# equalizer.net
KiCad netlist of a schematic drawn in EAGLE
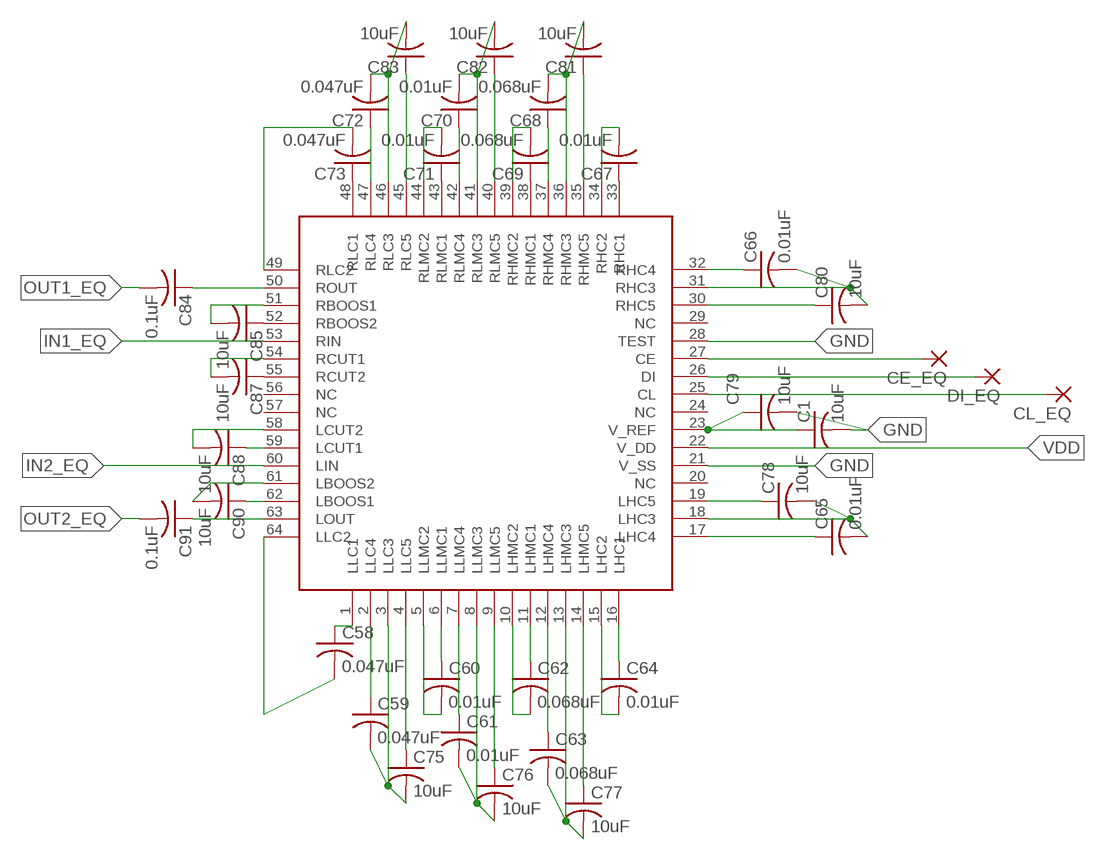
[diagram p0: schematic, sheet 1]

(export (version "E")
  (design (tool "Eeschema 10.0.6"))
  (components
    (comp (ref "C1")
      (value "10uF")
      (footprint "eagle-import:C0402")
      (libsource (lib "eagle-import") (part "C-USC0402"))
    )
    (comp (ref "C58")
      (value "0.047uF")
      (footprint "eagle-import:C0402")
      (libsource (lib "eagle-import") (part "C-USC0402"))
    )
    (comp (ref "C59")
      (value "0.047uF")
      (footprint "eagle-import:C0402")
      (libsource (lib "eagle-import") (part "C-USC0402"))
    )
    (comp (ref "C60")
      (value "0.01uF")
      (footprint "eagle-import:C0402")
      (libsource (lib "eagle-import") (part "C-USC0402"))
    )
    (comp (ref "C61")
      (value "0.01uF")
      (footprint "eagle-import:C0402")
      (libsource (lib "eagle-import") (part "C-USC0402"))
    )
    (comp (ref "C62")
      (value "0.068uF")
      (footprint "eagle-import:C0402")
      (libsource (lib "eagle-import") (part "C-USC0402"))
    )
    (comp (ref "C63")
      (value "0.068uF")
      (footprint "eagle-import:C0402")
      (libsource (lib "eagle-import") (part "C-USC0402"))
    )
    (comp (ref "C64")
      (value "0.01uF")
      (footprint "eagle-import:C0402")
      (libsource (lib "eagle-import") (part "C-USC0402"))
    )
    (comp (ref "C65")
      (value "0.01uF")
      (footprint "eagle-import:C0402")
      (libsource (lib "eagle-import") (part "C-USC0402"))
    )
    (comp (ref "C66")
      (value "0.01uF")
      (footprint "eagle-import:C0402")
      (libsource (lib "eagle-import") (part "C-USC0402"))
    )
    (comp (ref "C67")
      (value "0.01uF")
      (footprint "eagle-import:C0402")
      (libsource (lib "eagle-import") (part "C-USC0402"))
    )
    (comp (ref "C68")
      (value "0.068uF")
      (footprint "eagle-import:C0402")
      (libsource (lib "eagle-import") (part "C-USC0402"))
    )
    (comp (ref "C69")
      (value "0.068uF")
      (footprint "eagle-import:C0402")
      (libsource (lib "eagle-import") (part "C-USC0402"))
    )
    (comp (ref "C70")
      (value "0.01uF")
      (footprint "eagle-import:C0402")
      (libsource (lib "eagle-import") (part "C-USC0402"))
    )
    (comp (ref "C71")
      (value "0.01uF")
      (footprint "eagle-import:C0402")
      (libsource (lib "eagle-import") (part "C-USC0402"))
    )
    (comp (ref "C72")
      (value "0.047uF")
      (footprint "eagle-import:C0402")
      (libsource (lib "eagle-import") (part "C-USC0402"))
    )
    (comp (ref "C73")
      (value "0.047uF")
      (footprint "eagle-import:C0402")
      (libsource (lib "eagle-import") (part "C-USC0402"))
    )
    (comp (ref "C75")
      (value "10uF")
      (footprint "eagle-import:C0402")
      (libsource (lib "eagle-import") (part "C-USC0402"))
    )
    (comp (ref "C76")
      (value "10uF")
      (footprint "eagle-import:C0402")
      (libsource (lib "eagle-import") (part "C-USC0402"))
    )
    (comp (ref "C77")
      (value "10uF")
      (footprint "eagle-import:C0402")
      (libsource (lib "eagle-import") (part "C-USC0402"))
    )
    (comp (ref "C78")
      (value "10uF")
      (footprint "eagle-import:C0402")
      (libsource (lib "eagle-import") (part "C-USC0402"))
    )
    (comp (ref "C79")
      (value "10uF")
      (footprint "eagle-import:C0402")
      (libsource (lib "eagle-import") (part "C-USC0402"))
    )
    (comp (ref "C80")
      (value "10uF")
      (footprint "eagle-import:C0402")
      (libsource (lib "eagle-import") (part "C-USC0402"))
    )
    (comp (ref "C81")
      (value "10uF")
      (footprint "eagle-import:C0402")
      (libsource (lib "eagle-import") (part "C-USC0402"))
    )
    (comp (ref "C82")
      (value "10uF")
      (footprint "eagle-import:C0402")
      (libsource (lib "eagle-import") (part "C-USC0402"))
    )
    (comp (ref "C83")
      (value "10uF")
      (footprint "eagle-import:C0402")
      (libsource (lib "eagle-import") (part "C-USC0402"))
    )
    (comp (ref "C84")
      (value "0.1uF")
      (footprint "eagle-import:C0402")
      (libsource (lib "eagle-import") (part "C-USC0402"))
    )
    (comp (ref "C85")
      (value "10uF")
      (footprint "eagle-import:C0402")
      (libsource (lib "eagle-import") (part "C-USC0402"))
    )
    (comp (ref "C87")
      (value "10uF")
      (footprint "eagle-import:C0402")
      (libsource (lib "eagle-import") (part "C-USC0402"))
    )
    (comp (ref "C88")
      (value "10uF")
      (footprint "eagle-import:C0402")
      (libsource (lib "eagle-import") (part "C-USC0402"))
    )
    (comp (ref "C90")
      (value "10uF")
      (footprint "eagle-import:C0402")
      (libsource (lib "eagle-import") (part "C-USC0402"))
    )
    (comp (ref "C91")
      (value "0.1uF")
      (footprint "eagle-import:C0402")
      (libsource (lib "eagle-import") (part "C-USC0402"))
    )
    (comp (ref "CE_EQ")
      (value "SMD2")
      (footprint "eagle-import:SMD1,27-2,54")
      (libsource (lib "eagle-import") (part "SMD2"))
    )
    (comp (ref "CL_EQ")
      (value "SMD2")
      (footprint "eagle-import:SMD1,27-2,54")
      (libsource (lib "eagle-import") (part "SMD2"))
    )
    (comp (ref "DI_EQ")
      (value "SMD2")
      (footprint "eagle-import:SMD1,27-2,54")
      (libsource (lib "eagle-import") (part "SMD2"))
    )
    (comp (ref "U$14")
      (value "LC75281E")
      (footprint "eagle-import:QFP80P1720X1720X270-64N")
      (libsource (lib "eagle-import") (part "LC75281E"))
    )
  )
  (nets
    (net (code "1") (name "GND") (class "Default")
      (node (ref "C1") (pin "2") (pinfunction "2_2") (pintype "passive"))
      (node (ref "C79") (pin "2") (pinfunction "2_2") (pintype "passive"))
      (node (ref "U$14") (pin "21") (pinfunction "V_SS_21") (pintype "bidirectional"))
      (node (ref "U$14") (pin "28") (pinfunction "TEST_28") (pintype "bidirectional"))
    )
    (net (code "2") (name "IN1_EQ") (class "Default")
      (node (ref "U$14") (pin "53") (pinfunction "RIN_53") (pintype "bidirectional"))
    )
    (net (code "3") (name "IN2_EQ") (class "Default")
      (node (ref "U$14") (pin "60") (pinfunction "LIN_60") (pintype "bidirectional"))
    )
    (net (code "4") (name "Net-(CE_EQ-P)") (class "Default")
      (node (ref "CE_EQ") (pin "1") (pinfunction "P_1") (pintype "passive"))
      (node (ref "U$14") (pin "27") (pinfunction "CE_27") (pintype "bidirectional"))
    )
    (net (code "5") (name "Net-(CL_EQ-P)") (class "Default")
      (node (ref "CL_EQ") (pin "1") (pinfunction "P_1") (pintype "passive"))
      (node (ref "U$14") (pin "25") (pinfunction "CL_25") (pintype "bidirectional"))
    )
    (net (code "6") (name "Net-(DI_EQ-P)") (class "Default")
      (node (ref "DI_EQ") (pin "1") (pinfunction "P_1") (pintype "passive"))
      (node (ref "U$14") (pin "26") (pinfunction "DI_26") (pintype "bidirectional"))
    )
    (net (code "7") (name "Net-(U$14-LBOOS1)") (class "Default")
      (node (ref "C90") (pin "1") (pinfunction "1_1") (pintype "passive"))
      (node (ref "U$14") (pin "62") (pinfunction "LBOOS1_62") (pintype "bidirectional"))
    )
    (net (code "8") (name "Net-(U$14-LBOOS2)") (class "Default")
      (node (ref "C90") (pin "2") (pinfunction "2_2") (pintype "passive"))
      (node (ref "U$14") (pin "61") (pinfunction "LBOOS2_61") (pintype "bidirectional"))
    )
    (net (code "9") (name "Net-(U$14-LCUT1)") (class "Default")
      (node (ref "C88") (pin "1") (pinfunction "1_1") (pintype "passive"))
      (node (ref "U$14") (pin "59") (pinfunction "LCUT1_59") (pintype "bidirectional"))
    )
    (net (code "10") (name "Net-(U$14-LCUT2)") (class "Default")
      (node (ref "C88") (pin "2") (pinfunction "2_2") (pintype "passive"))
      (node (ref "U$14") (pin "58") (pinfunction "LCUT2_58") (pintype "bidirectional"))
    )
    (net (code "11") (name "Net-(U$14-LHC1)") (class "Default")
      (node (ref "C64") (pin "1") (pinfunction "1_1") (pintype "passive"))
      (node (ref "U$14") (pin "16") (pinfunction "LHC1_16") (pintype "bidirectional"))
    )
    (net (code "12") (name "Net-(U$14-LHC2)") (class "Default")
      (node (ref "C64") (pin "2") (pinfunction "2_2") (pintype "passive"))
      (node (ref "U$14") (pin "15") (pinfunction "LHC2_15") (pintype "bidirectional"))
    )
    (net (code "13") (name "Net-(U$14-LHC3)") (class "Default")
      (node (ref "C65") (pin "2") (pinfunction "2_2") (pintype "passive"))
      (node (ref "C78") (pin "2") (pinfunction "2_2") (pintype "passive"))
      (node (ref "U$14") (pin "18") (pinfunction "LHC3_18") (pintype "bidirectional"))
    )
    (net (code "14") (name "Net-(U$14-LHC4)") (class "Default")
      (node (ref "C65") (pin "1") (pinfunction "1_1") (pintype "passive"))
      (node (ref "U$14") (pin "17") (pinfunction "LHC4_17") (pintype "bidirectional"))
    )
    (net (code "15") (name "Net-(U$14-LHC5)") (class "Default")
      (node (ref "C78") (pin "1") (pinfunction "1_1") (pintype "passive"))
      (node (ref "U$14") (pin "19") (pinfunction "LHC5_19") (pintype "bidirectional"))
    )
    (net (code "16") (name "Net-(U$14-LHMC1)") (class "Default")
      (node (ref "C62") (pin "1") (pinfunction "1_1") (pintype "passive"))
      (node (ref "U$14") (pin "11") (pinfunction "LHMC1_11") (pintype "bidirectional"))
    )
    (net (code "17") (name "Net-(U$14-LHMC2)") (class "Default")
      (node (ref "C62") (pin "2") (pinfunction "2_2") (pintype "passive"))
      (node (ref "U$14") (pin "10") (pinfunction "LHMC2_10") (pintype "bidirectional"))
    )
    (net (code "18") (name "Net-(U$14-LHMC3)") (class "Default")
      (node (ref "C63") (pin "2") (pinfunction "2_2") (pintype "passive"))
      (node (ref "C77") (pin "2") (pinfunction "2_2") (pintype "passive"))
      (node (ref "U$14") (pin "13") (pinfunction "LHMC3_13") (pintype "bidirectional"))
    )
    (net (code "19") (name "Net-(U$14-LHMC4)") (class "Default")
      (node (ref "C63") (pin "1") (pinfunction "1_1") (pintype "passive"))
      (node (ref "U$14") (pin "12") (pinfunction "LHMC4_12") (pintype "bidirectional"))
    )
    (net (code "20") (name "Net-(U$14-LHMC5)") (class "Default")
      (node (ref "C77") (pin "1") (pinfunction "1_1") (pintype "passive"))
      (node (ref "U$14") (pin "14") (pinfunction "LHMC5_14") (pintype "bidirectional"))
    )
    (net (code "21") (name "Net-(U$14-LLC1)") (class "Default")
      (node (ref "C58") (pin "1") (pinfunction "1_1") (pintype "passive"))
      (node (ref "U$14") (pin "1") (pinfunction "LLC1_1") (pintype "bidirectional"))
    )
    (net (code "22") (name "Net-(U$14-LLC2)") (class "Default")
      (node (ref "C58") (pin "2") (pinfunction "2_2") (pintype "passive"))
      (node (ref "U$14") (pin "64") (pinfunction "LLC2_64") (pintype "bidirectional"))
    )
    (net (code "23") (name "Net-(U$14-LLC3)") (class "Default")
      (node (ref "C59") (pin "2") (pinfunction "2_2") (pintype "passive"))
      (node (ref "C75") (pin "2") (pinfunction "2_2") (pintype "passive"))
      (node (ref "U$14") (pin "3") (pinfunction "LLC3_3") (pintype "bidirectional"))
    )
    (net (code "24") (name "Net-(U$14-LLC4)") (class "Default")
      (node (ref "C59") (pin "1") (pinfunction "1_1") (pintype "passive"))
      (node (ref "U$14") (pin "2") (pinfunction "LLC4_2") (pintype "bidirectional"))
    )
    (net (code "25") (name "Net-(U$14-LLC5)") (class "Default")
      (node (ref "C75") (pin "1") (pinfunction "1_1") (pintype "passive"))
      (node (ref "U$14") (pin "4") (pinfunction "LLC5_4") (pintype "bidirectional"))
    )
    (net (code "26") (name "Net-(U$14-LLMC1)") (class "Default")
      (node (ref "C60") (pin "1") (pinfunction "1_1") (pintype "passive"))
      (node (ref "U$14") (pin "6") (pinfunction "LLMC1_6") (pintype "bidirectional"))
    )
    (net (code "27") (name "Net-(U$14-LLMC2)") (class "Default")
      (node (ref "C60") (pin "2") (pinfunction "2_2") (pintype "passive"))
      (node (ref "U$14") (pin "5") (pinfunction "LLMC2_5") (pintype "bidirectional"))
    )
    (net (code "28") (name "Net-(U$14-LLMC3)") (class "Default")
      (node (ref "C61") (pin "2") (pinfunction "2_2") (pintype "passive"))
      (node (ref "C76") (pin "2") (pinfunction "2_2") (pintype "passive"))
      (node (ref "U$14") (pin "8") (pinfunction "LLMC3_8") (pintype "bidirectional"))
    )
    (net (code "29") (name "Net-(U$14-LLMC4)") (class "Default")
      (node (ref "C61") (pin "1") (pinfunction "1_1") (pintype "passive"))
      (node (ref "U$14") (pin "7") (pinfunction "LLMC4_7") (pintype "bidirectional"))
    )
    (net (code "30") (name "Net-(U$14-LLMC5)") (class "Default")
      (node (ref "C76") (pin "1") (pinfunction "1_1") (pintype "passive"))
      (node (ref "U$14") (pin "9") (pinfunction "LLMC5_9") (pintype "bidirectional"))
    )
    (net (code "31") (name "Net-(U$14-LOUT)") (class "Default")
      (node (ref "C91") (pin "1") (pinfunction "1_1") (pintype "passive"))
      (node (ref "U$14") (pin "63") (pinfunction "LOUT_63") (pintype "bidirectional"))
    )
    (net (code "32") (name "Net-(U$14-RBOOS1)") (class "Default")
      (node (ref "C85") (pin "2") (pinfunction "2_2") (pintype "passive"))
      (node (ref "U$14") (pin "51") (pinfunction "RBOOS1_51") (pintype "bidirectional"))
    )
    (net (code "33") (name "Net-(U$14-RBOOS2)") (class "Default")
      (node (ref "C85") (pin "1") (pinfunction "1_1") (pintype "passive"))
      (node (ref "U$14") (pin "52") (pinfunction "RBOOS2_52") (pintype "bidirectional"))
    )
    (net (code "34") (name "Net-(U$14-RCUT1)") (class "Default")
      (node (ref "C87") (pin "2") (pinfunction "2_2") (pintype "passive"))
      (node (ref "U$14") (pin "54") (pinfunction "RCUT1_54") (pintype "bidirectional"))
    )
    (net (code "35") (name "Net-(U$14-RCUT2)") (class "Default")
      (node (ref "C87") (pin "1") (pinfunction "1_1") (pintype "passive"))
      (node (ref "U$14") (pin "55") (pinfunction "RCUT2_55") (pintype "bidirectional"))
    )
    (net (code "36") (name "Net-(U$14-RHC1)") (class "Default")
      (node (ref "C67") (pin "1") (pinfunction "1_1") (pintype "passive"))
      (node (ref "U$14") (pin "33") (pinfunction "RHC1_33") (pintype "bidirectional"))
    )
    (net (code "37") (name "Net-(U$14-RHC2)") (class "Default")
      (node (ref "C67") (pin "2") (pinfunction "2_2") (pintype "passive"))
      (node (ref "U$14") (pin "34") (pinfunction "RHC2_34") (pintype "bidirectional"))
    )
    (net (code "38") (name "Net-(U$14-RHC3)") (class "Default")
      (node (ref "C66") (pin "2") (pinfunction "2_2") (pintype "passive"))
      (node (ref "C80") (pin "2") (pinfunction "2_2") (pintype "passive"))
      (node (ref "U$14") (pin "31") (pinfunction "RHC3_31") (pintype "bidirectional"))
    )
    (net (code "39") (name "Net-(U$14-RHC4)") (class "Default")
      (node (ref "C66") (pin "1") (pinfunction "1_1") (pintype "passive"))
      (node (ref "U$14") (pin "32") (pinfunction "RHC4_32") (pintype "bidirectional"))
    )
    (net (code "40") (name "Net-(U$14-RHC5)") (class "Default")
      (node (ref "C80") (pin "1") (pinfunction "1_1") (pintype "passive"))
      (node (ref "U$14") (pin "30") (pinfunction "RHC5_30") (pintype "bidirectional"))
    )
    (net (code "41") (name "Net-(U$14-RHMC1)") (class "Default")
      (node (ref "C69") (pin "1") (pinfunction "1_1") (pintype "passive"))
      (node (ref "U$14") (pin "38") (pinfunction "RHMC1_38") (pintype "bidirectional"))
    )
    (net (code "42") (name "Net-(U$14-RHMC2)") (class "Default")
      (node (ref "C69") (pin "2") (pinfunction "2_2") (pintype "passive"))
      (node (ref "U$14") (pin "39") (pinfunction "RHMC2_39") (pintype "bidirectional"))
    )
    (net (code "43") (name "Net-(U$14-RHMC3)") (class "Default")
      (node (ref "C68") (pin "2") (pinfunction "2_2") (pintype "passive"))
      (node (ref "C81") (pin "2") (pinfunction "2_2") (pintype "passive"))
      (node (ref "U$14") (pin "36") (pinfunction "RHMC3_36") (pintype "bidirectional"))
    )
    (net (code "44") (name "Net-(U$14-RHMC4)") (class "Default")
      (node (ref "C68") (pin "1") (pinfunction "1_1") (pintype "passive"))
      (node (ref "U$14") (pin "37") (pinfunction "RHMC4_37") (pintype "bidirectional"))
    )
    (net (code "45") (name "Net-(U$14-RHMC5)") (class "Default")
      (node (ref "C81") (pin "1") (pinfunction "1_1") (pintype "passive"))
      (node (ref "U$14") (pin "35") (pinfunction "RHMC5_35") (pintype "bidirectional"))
    )
    (net (code "46") (name "Net-(U$14-RLC1)") (class "Default")
      (node (ref "C73") (pin "1") (pinfunction "1_1") (pintype "passive"))
      (node (ref "U$14") (pin "48") (pinfunction "RLC1_48") (pintype "bidirectional"))
    )
    (net (code "47") (name "Net-(U$14-RLC2)") (class "Default")
      (node (ref "C73") (pin "2") (pinfunction "2_2") (pintype "passive"))
      (node (ref "U$14") (pin "49") (pinfunction "RLC2_49") (pintype "bidirectional"))
    )
    (net (code "48") (name "Net-(U$14-RLC3)") (class "Default")
      (node (ref "C72") (pin "2") (pinfunction "2_2") (pintype "passive"))
      (node (ref "C83") (pin "2") (pinfunction "2_2") (pintype "passive"))
      (node (ref "U$14") (pin "46") (pinfunction "RLC3_46") (pintype "bidirectional"))
    )
    (net (code "49") (name "Net-(U$14-RLC4)") (class "Default")
      (node (ref "C72") (pin "1") (pinfunction "1_1") (pintype "passive"))
      (node (ref "U$14") (pin "47") (pinfunction "RLC4_47") (pintype "bidirectional"))
    )
    (net (code "50") (name "Net-(U$14-RLC5)") (class "Default")
      (node (ref "C83") (pin "1") (pinfunction "1_1") (pintype "passive"))
      (node (ref "U$14") (pin "45") (pinfunction "RLC5_45") (pintype "bidirectional"))
    )
    (net (code "51") (name "Net-(U$14-RLMC1)") (class "Default")
      (node (ref "C71") (pin "1") (pinfunction "1_1") (pintype "passive"))
      (node (ref "U$14") (pin "43") (pinfunction "RLMC1_43") (pintype "bidirectional"))
    )
    (net (code "52") (name "Net-(U$14-RLMC2)") (class "Default")
      (node (ref "C71") (pin "2") (pinfunction "2_2") (pintype "passive"))
      (node (ref "U$14") (pin "44") (pinfunction "RLMC2_44") (pintype "bidirectional"))
    )
    (net (code "53") (name "Net-(U$14-RLMC3)") (class "Default")
      (node (ref "C70") (pin "2") (pinfunction "2_2") (pintype "passive"))
      (node (ref "C82") (pin "2") (pinfunction "2_2") (pintype "passive"))
      (node (ref "U$14") (pin "41") (pinfunction "RLMC3_41") (pintype "bidirectional"))
    )
    (net (code "54") (name "Net-(U$14-RLMC4)") (class "Default")
      (node (ref "C70") (pin "1") (pinfunction "1_1") (pintype "passive"))
      (node (ref "U$14") (pin "42") (pinfunction "RLMC4_42") (pintype "bidirectional"))
    )
    (net (code "55") (name "Net-(U$14-RLMC5)") (class "Default")
      (node (ref "C82") (pin "1") (pinfunction "1_1") (pintype "passive"))
      (node (ref "U$14") (pin "40") (pinfunction "RLMC5_40") (pintype "bidirectional"))
    )
    (net (code "56") (name "Net-(U$14-ROUT)") (class "Default")
      (node (ref "C84") (pin "1") (pinfunction "1_1") (pintype "passive"))
      (node (ref "U$14") (pin "50") (pinfunction "ROUT_50") (pintype "bidirectional"))
    )
    (net (code "57") (name "Net-(U$14-V_REF)") (class "Default")
      (node (ref "C1") (pin "1") (pinfunction "1_1") (pintype "passive"))
      (node (ref "C79") (pin "1") (pinfunction "1_1") (pintype "passive"))
      (node (ref "U$14") (pin "23") (pinfunction "V_REF_23") (pintype "bidirectional"))
    )
    (net (code "58") (name "OUT1_EQ") (class "Default")
      (node (ref "C84") (pin "2") (pinfunction "2_2") (pintype "passive"))
    )
    (net (code "59") (name "OUT2_EQ") (class "Default")
      (node (ref "C91") (pin "2") (pinfunction "2_2") (pintype "passive"))
    )
    (net (code "60") (name "VDD") (class "Default")
      (node (ref "U$14") (pin "22") (pinfunction "V_DD_22") (pintype "bidirectional"))
    )
    (net (code "61") (name "unconnected-(U$14-NC-Pad20)") (class "Default")
      (node (ref "U$14") (pin "20") (pinfunction "NC_20") (pintype "bidirectional"))
    )
    (net (code "62") (name "unconnected-(U$14-NC-Pad24)") (class "Default")
      (node (ref "U$14") (pin "24") (pinfunction "NC_24") (pintype "bidirectional"))
    )
    (net (code "63") (name "unconnected-(U$14-NC-Pad29)") (class "Default")
      (node (ref "U$14") (pin "29") (pinfunction "NC_29") (pintype "bidirectional"))
    )
    (net (code "64") (name "unconnected-(U$14-NC-Pad56)") (class "Default")
      (node (ref "U$14") (pin "56") (pinfunction "NC_56") (pintype "bidirectional"))
    )
    (net (code "65") (name "unconnected-(U$14-NC-Pad57)") (class "Default")
      (node (ref "U$14") (pin "57") (pinfunction "NC_57") (pintype "bidirectional"))
    )
  )
)
